# Pool_Controller-v3.net
KiCad netlist of a schematic drawn in EAGLE
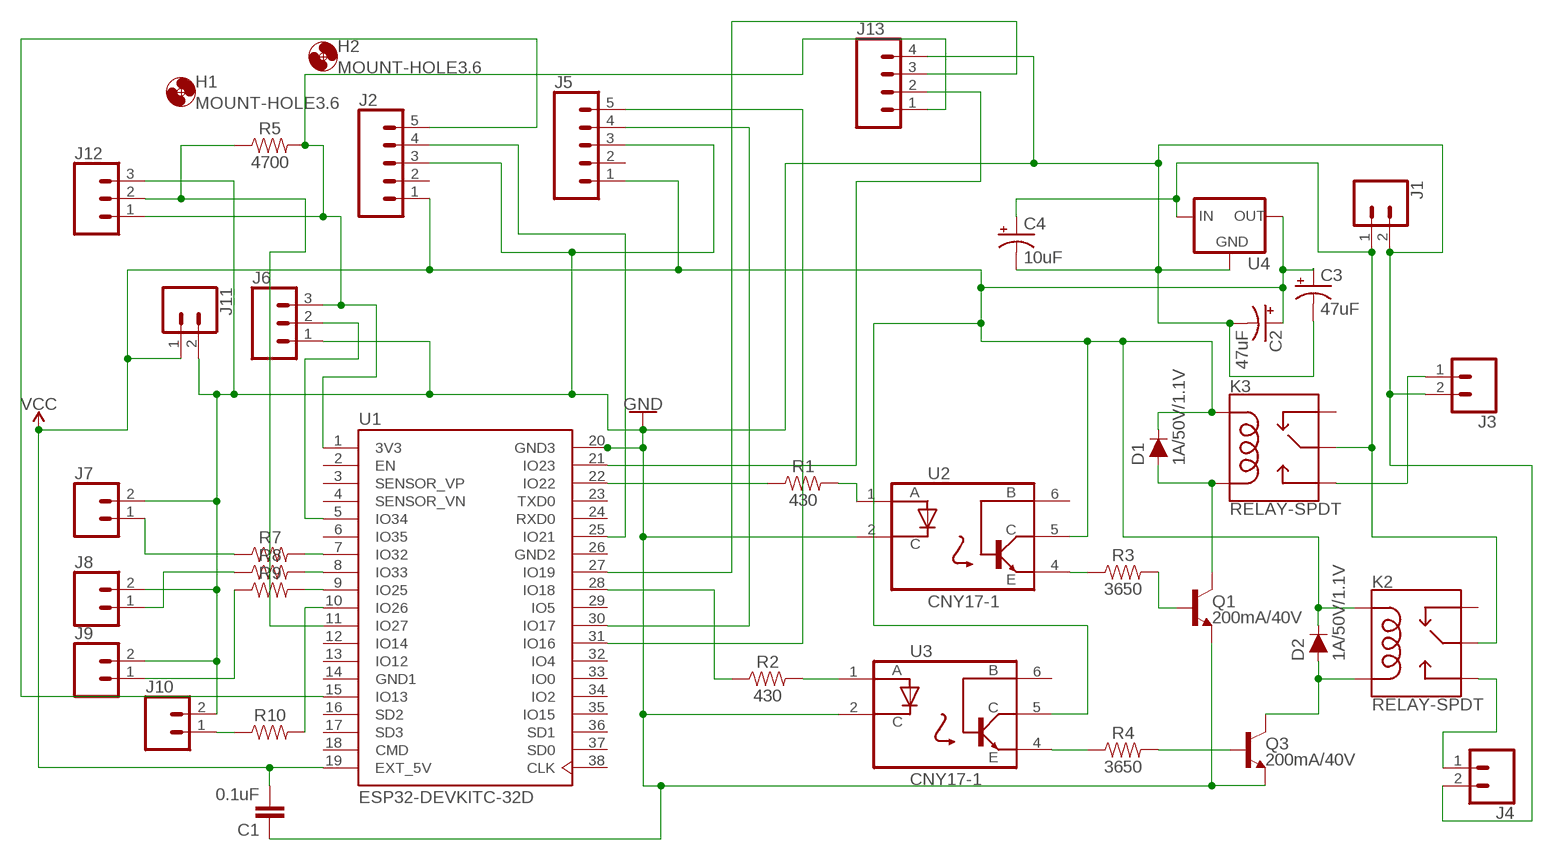
[diagram p0: schematic, sheet 1]

(export (version "E")
  (design (tool "Eeschema 10.0.6"))
  (components
    (comp (ref "C1")
      (value "0.1uF")
      (footprint "eagle-import:CAP-PTH-SMALL-KIT")
      (libsource (lib "eagle-import") (part "0.1UF-KIT-EZ-50V-20%"))
    )
    (comp (ref "C2")
      (value "47uF")
      (footprint "eagle-import:CPOL-RADIAL-2.5MM-5MM-KIT")
      (libsource (lib "eagle-import") (part "SparkFun-Capacitors_510_10UF-POLAR-RADIAL-2.5MM-KIT-25V-20%"))
    )
    (comp (ref "C3")
      (value "47uF")
      (footprint "eagle-import:CPOL-RADIAL-2.5MM-5MM")
      (libsource (lib "eagle-import") (part "10UF-POLAR-RADIAL-2.5MM-25V-20%"))
    )
    (comp (ref "C4")
      (value "10uF")
      (footprint "eagle-import:CPOL-RADIAL-2.5MM-5MM")
      (libsource (lib "eagle-import") (part "10UF-POLAR-RADIAL-2.5MM-25V-20%"))
    )
    (comp (ref "D1")
      (value "1A/50V/1.1V")
      (footprint "eagle-import:DIODE-1N4001")
      (libsource (lib "eagle-import") (part "DIODE-PTH"))
    )
    (comp (ref "D2")
      (value "1A/50V/1.1V")
      (footprint "eagle-import:DIODE-1N4001")
      (libsource (lib "eagle-import") (part "DIODE-PTH"))
    )
    (comp (ref "H1")
      (value "MOUNT-HOLE3.6")
      (footprint "eagle-import:3,6")
      (libsource (lib "eagle-import") (part "MOUNT-HOLE3.6"))
    )
    (comp (ref "H2")
      (value "MOUNT-HOLE3.6")
      (footprint "eagle-import:3,6")
      (libsource (lib "eagle-import") (part "MOUNT-HOLE3.6"))
    )
    (comp (ref "J1")
      (value "CONN_023.5MM")
      (footprint "eagle-import:SCREWTERMINAL-3.5MM-2")
      (libsource (lib "eagle-import") (part "CONN_023.5MM"))
    )
    (comp (ref "J2")
      (value "CONN_05")
      (footprint "eagle-import:1X05")
      (libsource (lib "eagle-import") (part "CONN_05"))
    )
    (comp (ref "J3")
      (value "CONN_023.5MM")
      (footprint "eagle-import:SCREWTERMINAL-3.5MM-2")
      (libsource (lib "eagle-import") (part "CONN_023.5MM"))
    )
    (comp (ref "J4")
      (value "CONN_023.5MM")
      (footprint "eagle-import:SCREWTERMINAL-3.5MM-2")
      (libsource (lib "eagle-import") (part "CONN_023.5MM"))
    )
    (comp (ref "J5")
      (value "CONN_05")
      (footprint "eagle-import:1X05")
      (libsource (lib "eagle-import") (part "CONN_05"))
    )
    (comp (ref "J6")
      (value "CONN_03SCREW")
      (footprint "eagle-import:SCREWTERMINAL-3.5MM-3")
      (libsource (lib "eagle-import") (part "CONN_03SCREW"))
    )
    (comp (ref "J7")
      (value "CONN_02")
      (footprint "eagle-import:1X02")
      (libsource (lib "eagle-import") (part "CONN_02"))
    )
    (comp (ref "J8")
      (value "CONN_02")
      (footprint "eagle-import:1X02")
      (libsource (lib "eagle-import") (part "CONN_02"))
    )
    (comp (ref "J9")
      (value "CONN_02")
      (footprint "eagle-import:1X02")
      (libsource (lib "eagle-import") (part "CONN_02"))
    )
    (comp (ref "J10")
      (value "CONN_02")
      (footprint "eagle-import:1X02")
      (libsource (lib "eagle-import") (part "CONN_02"))
    )
    (comp (ref "J11")
      (value "CONN_023.5MM")
      (footprint "eagle-import:SCREWTERMINAL-3.5MM-2")
      (libsource (lib "eagle-import") (part "CONN_023.5MM"))
    )
    (comp (ref "J12")
      (value "CONN_03SCREW")
      (footprint "eagle-import:SCREWTERMINAL-3.5MM-3")
      (libsource (lib "eagle-import") (part "CONN_03SCREW"))
    )
    (comp (ref "J13")
      (value "CONN_04SCREW")
      (footprint "eagle-import:SCREWTERMINAL-3.5MM-4")
      (libsource (lib "eagle-import") (part "CONN_04SCREW"))
    )
    (comp (ref "K2")
      (value "RELAY-SPDT")
      (footprint "eagle-import:RELAY_G5LE")
      (libsource (lib "eagle-import") (part "RELAY-SPDT"))
    )
    (comp (ref "K3")
      (value "RELAY-SPDT")
      (footprint "eagle-import:RELAY_G5LE")
      (libsource (lib "eagle-import") (part "RELAY-SPDT"))
    )
    (comp (ref "Q1")
      (value "200mA/40V")
      (footprint "eagle-import:TO-92")
      (libsource (lib "eagle-import") (part "TRANS_NPN-2N3904"))
    )
    (comp (ref "Q3")
      (value "200mA/40V")
      (footprint "eagle-import:TO-92")
      (libsource (lib "eagle-import") (part "TRANS_NPN-2N3904"))
    )
    (comp (ref "R1")
      (value "430")
      (footprint "eagle-import:AXIAL-0.3")
      (libsource (lib "eagle-import") (part "RESISTORAXIAL-0.3"))
    )
    (comp (ref "R2")
      (value "430")
      (footprint "eagle-import:AXIAL-0.3")
      (libsource (lib "eagle-import") (part "RESISTORAXIAL-0.3"))
    )
    (comp (ref "R3")
      (value "3650")
      (footprint "eagle-import:AXIAL-0.3")
      (libsource (lib "eagle-import") (part "RESISTORAXIAL-0.3"))
    )
    (comp (ref "R4")
      (value "3650")
      (footprint "eagle-import:AXIAL-0.3")
      (libsource (lib "eagle-import") (part "RESISTORAXIAL-0.3"))
    )
    (comp (ref "R5")
      (value "4700")
      (footprint "eagle-import:AXIAL-0.3")
      (libsource (lib "eagle-import") (part "SparkFun-Resistors_532_RESISTORAXIAL-0.3"))
    )
    (comp (ref "R7")
      (value "RESISTORAXIAL-0.3")
      (footprint "eagle-import:AXIAL-0.3")
      (libsource (lib "eagle-import") (part "RESISTORAXIAL-0.3"))
    )
    (comp (ref "R8")
      (value "RESISTORAXIAL-0.3")
      (footprint "eagle-import:AXIAL-0.3")
      (libsource (lib "eagle-import") (part "RESISTORAXIAL-0.3"))
    )
    (comp (ref "R9")
      (value "RESISTORAXIAL-0.3")
      (footprint "eagle-import:AXIAL-0.3")
      (libsource (lib "eagle-import") (part "RESISTORAXIAL-0.3"))
    )
    (comp (ref "R10")
      (value "RESISTORAXIAL-0.3")
      (footprint "eagle-import:AXIAL-0.3")
      (libsource (lib "eagle-import") (part "RESISTORAXIAL-0.3"))
    )
    (comp (ref "U1")
      (value "ESP32-DEVKITC-32D")
      (footprint "eagle-import:MODULE_ESP32-DEVKITC-32D")
      (fields (field (name "MF") "Espressif Systems"))
      (libsource (lib "eagle-import") (part "ESP32-DEVKITC-32D"))
    )
    (comp (ref "U2")
      (value "CNY17-1")
      (footprint "eagle-import:DIP762W50P254L730H410Q6")
      (fields (field (name "MF") "Vishay"))
      (libsource (lib "eagle-import") (part "CNY17-1"))
    )
    (comp (ref "U3")
      (value "CNY17-1")
      (footprint "eagle-import:DIP762W50P254L730H410Q6")
      (fields (field (name "MF") "Vishay"))
      (libsource (lib "eagle-import") (part "CNY17-1"))
    )
    (comp (ref "U4")
      (value "V_REG_78XXSIDE")
      (footprint "eagle-import:78XXL")
      (libsource (lib "eagle-import") (part "V_REG_78XXSIDE"))
    )
  )
  (nets
    (net (code "1") (name "/GND1") (class "Default")
      (node (ref "U1") (pin "14") (pinfunction "GND1_14") (pintype "power_in"))
    )
    (net (code "2") (name "/GND2") (class "Default")
      (node (ref "U1") (pin "26") (pinfunction "GND2_26") (pintype "power_in"))
    )
    (net (code "3") (name "GND") (class "Default")
      (node (ref "C1") (pin "1") (pinfunction "1_1") (pintype "passive"))
      (node (ref "C2") (pin "2") (pinfunction "-_2") (pintype "passive"))
      (node (ref "C3") (pin "2") (pinfunction "-_2") (pintype "passive"))
      (node (ref "C4") (pin "2") (pinfunction "-_2") (pintype "passive"))
      (node (ref "J1") (pin "2") (pinfunction "2_2") (pintype "passive"))
      (node (ref "J10") (pin "2") (pinfunction "2_2") (pintype "passive"))
      (node (ref "J11") (pin "2") (pinfunction "2_2") (pintype "passive"))
      (node (ref "J12") (pin "3") (pinfunction "3_3") (pintype "passive"))
      (node (ref "J13") (pin "4") (pinfunction "4_4") (pintype "passive"))
      (node (ref "J2") (pin "3") (pinfunction "3_3") (pintype "passive"))
      (node (ref "J3") (pin "2") (pinfunction "2_2") (pintype "passive"))
      (node (ref "J4") (pin "2") (pinfunction "2_2") (pintype "passive"))
      (node (ref "J5") (pin "3") (pinfunction "3_3") (pintype "passive"))
      (node (ref "J6") (pin "1") (pinfunction "1_1") (pintype "passive"))
      (node (ref "J7") (pin "2") (pinfunction "2_2") (pintype "passive"))
      (node (ref "J8") (pin "2") (pinfunction "2_2") (pintype "passive"))
      (node (ref "J9") (pin "2") (pinfunction "2_2") (pintype "passive"))
      (node (ref "Q1") (pin "1") (pinfunction "E_1") (pintype "passive"))
      (node (ref "Q3") (pin "1") (pinfunction "E_1") (pintype "passive"))
      (node (ref "U1") (pin "20") (pinfunction "GND3_20") (pintype "power_in"))
      (node (ref "U2") (pin "2") (pinfunction "C_2") (pintype "passive"))
      (node (ref "U3") (pin "2") (pinfunction "C_2") (pintype "passive"))
      (node (ref "U4") (pin "GND") (pinfunction "GND_GND") (pintype "input"))
    )
    (net (code "4") (name "Net-(C4-+)") (class "Default")
      (node (ref "C4") (pin "1") (pinfunction "+_1") (pintype "passive"))
      (node (ref "J1") (pin "1") (pinfunction "1_1") (pintype "passive"))
      (node (ref "K2") (pin "1") (pinfunction "MAIN_1") (pintype "bidirectional"))
      (node (ref "K3") (pin "1") (pinfunction "MAIN_1") (pintype "bidirectional"))
      (node (ref "U4") (pin "IN") (pinfunction "IN_IN") (pintype "input"))
    )
    (net (code "5") (name "Net-(K2-COIL2)") (class "Default")
      (node (ref "D2") (pin "A") (pinfunction "A_A") (pintype "passive"))
      (node (ref "K2") (pin "5") (pinfunction "COIL2_5") (pintype "bidirectional"))
      (node (ref "Q3") (pin "3") (pinfunction "C_3") (pintype "passive"))
    )
    (net (code "6") (name "Net-(K2-NO)") (class "Default")
      (node (ref "J4") (pin "1") (pinfunction "1_1") (pintype "passive"))
      (node (ref "K2") (pin "3") (pinfunction "NO_3") (pintype "bidirectional"))
    )
    (net (code "7") (name "Net-(K3-COIL2)") (class "Default")
      (node (ref "D1") (pin "A") (pinfunction "A_A") (pintype "passive"))
      (node (ref "K3") (pin "5") (pinfunction "COIL2_5") (pintype "bidirectional"))
      (node (ref "Q1") (pin "3") (pinfunction "C_3") (pintype "passive"))
    )
    (net (code "8") (name "Net-(K3-NO)") (class "Default")
      (node (ref "J3") (pin "1") (pinfunction "1_1") (pintype "passive"))
      (node (ref "K3") (pin "3") (pinfunction "NO_3") (pintype "bidirectional"))
    )
    (net (code "9") (name "Net-(Q1-B)") (class "Default")
      (node (ref "Q1") (pin "2") (pinfunction "B_2") (pintype "passive"))
      (node (ref "R3") (pin "P$2") (pinfunction "2_P$2") (pintype "passive"))
    )
    (net (code "10") (name "Net-(Q3-B)") (class "Default")
      (node (ref "Q3") (pin "2") (pinfunction "B_2") (pintype "passive"))
      (node (ref "R4") (pin "P$2") (pinfunction "2_P$2") (pintype "passive"))
    )
    (net (code "11") (name "Net-(R1-1)") (class "Default")
      (node (ref "R1") (pin "P$1") (pinfunction "1_P$1") (pintype "passive"))
      (node (ref "U1") (pin "22") (pinfunction "IO22_22") (pintype "bidirectional"))
    )
    (net (code "12") (name "Net-(R1-2)") (class "Default")
      (node (ref "R1") (pin "P$2") (pinfunction "2_P$2") (pintype "passive"))
      (node (ref "U2") (pin "1") (pinfunction "A_1") (pintype "passive"))
    )
    (net (code "13") (name "Net-(R2-1)") (class "Default")
      (node (ref "R2") (pin "P$1") (pinfunction "1_P$1") (pintype "passive"))
      (node (ref "U1") (pin "28") (pinfunction "IO18_28") (pintype "bidirectional"))
    )
    (net (code "14") (name "Net-(R2-2)") (class "Default")
      (node (ref "R2") (pin "P$2") (pinfunction "2_P$2") (pintype "passive"))
      (node (ref "U3") (pin "1") (pinfunction "A_1") (pintype "passive"))
    )
    (net (code "15") (name "Net-(R3-1)") (class "Default")
      (node (ref "R3") (pin "P$1") (pinfunction "1_P$1") (pintype "passive"))
      (node (ref "U2") (pin "4") (pinfunction "E_4") (pintype "passive"))
    )
    (net (code "16") (name "Net-(R4-1)") (class "Default")
      (node (ref "R4") (pin "P$1") (pinfunction "1_P$1") (pintype "passive"))
      (node (ref "U3") (pin "4") (pinfunction "E_4") (pintype "passive"))
    )
    (net (code "17") (name "Net-(R5-1)") (class "Default")
      (node (ref "J12") (pin "2") (pinfunction "2_2") (pintype "passive"))
      (node (ref "R5") (pin "P$1") (pinfunction "1_P$1") (pintype "passive"))
      (node (ref "U1") (pin "11") (pinfunction "IO27_11") (pintype "bidirectional"))
    )
    (net (code "18") (name "Net-(R5-2)") (class "Default")
      (node (ref "J12") (pin "1") (pinfunction "1_1") (pintype "passive"))
      (node (ref "J13") (pin "1") (pinfunction "1_1") (pintype "passive"))
      (node (ref "J6") (pin "3") (pinfunction "3_3") (pintype "passive"))
      (node (ref "R5") (pin "P$2") (pinfunction "2_P$2") (pintype "passive"))
      (node (ref "U1") (pin "1") (pinfunction "3V3_1") (pintype "power_in"))
    )
    (net (code "19") (name "Net-(R7-1)") (class "Default")
      (node (ref "J7") (pin "1") (pinfunction "1_1") (pintype "passive"))
      (node (ref "R7") (pin "P$1") (pinfunction "1_P$1") (pintype "passive"))
    )
    (net (code "20") (name "Net-(R7-2)") (class "Default")
      (node (ref "R7") (pin "P$2") (pinfunction "2_P$2") (pintype "passive"))
      (node (ref "U1") (pin "7") (pinfunction "IO32_7") (pintype "bidirectional"))
    )
    (net (code "21") (name "Net-(R8-1)") (class "Default")
      (node (ref "J8") (pin "1") (pinfunction "1_1") (pintype "passive"))
      (node (ref "R8") (pin "P$1") (pinfunction "1_P$1") (pintype "passive"))
    )
    (net (code "22") (name "Net-(R8-2)") (class "Default")
      (node (ref "R8") (pin "P$2") (pinfunction "2_P$2") (pintype "passive"))
      (node (ref "U1") (pin "8") (pinfunction "IO33_8") (pintype "bidirectional"))
    )
    (net (code "23") (name "Net-(R9-1)") (class "Default")
      (node (ref "J9") (pin "1") (pinfunction "1_1") (pintype "passive"))
      (node (ref "R9") (pin "P$1") (pinfunction "1_P$1") (pintype "passive"))
    )
    (net (code "24") (name "Net-(R9-2)") (class "Default")
      (node (ref "R9") (pin "P$2") (pinfunction "2_P$2") (pintype "passive"))
      (node (ref "U1") (pin "9") (pinfunction "IO25_9") (pintype "bidirectional"))
    )
    (net (code "25") (name "Net-(R10-1)") (class "Default")
      (node (ref "J10") (pin "1") (pinfunction "1_1") (pintype "passive"))
      (node (ref "R10") (pin "P$1") (pinfunction "1_P$1") (pintype "passive"))
    )
    (net (code "26") (name "Net-(R10-2)") (class "Default")
      (node (ref "R10") (pin "P$2") (pinfunction "2_P$2") (pintype "passive"))
      (node (ref "U1") (pin "10") (pinfunction "IO26_10") (pintype "bidirectional"))
    )
    (net (code "27") (name "Net-(U1-IO13)") (class "Default")
      (node (ref "J2") (pin "5") (pinfunction "5_5") (pintype "passive"))
      (node (ref "U1") (pin "15") (pinfunction "IO13_15") (pintype "bidirectional"))
    )
    (net (code "28") (name "Net-(U1-IO16)") (class "Default")
      (node (ref "J5") (pin "5") (pinfunction "5_5") (pintype "passive"))
      (node (ref "U1") (pin "31") (pinfunction "IO16_31") (pintype "bidirectional"))
    )
    (net (code "29") (name "Net-(U1-IO17)") (class "Default")
      (node (ref "J5") (pin "4") (pinfunction "4_4") (pintype "passive"))
      (node (ref "U1") (pin "30") (pinfunction "IO17_30") (pintype "bidirectional"))
    )
    (net (code "30") (name "Net-(U1-IO19)") (class "Default")
      (node (ref "J13") (pin "3") (pinfunction "3_3") (pintype "passive"))
      (node (ref "U1") (pin "27") (pinfunction "IO19_27") (pintype "bidirectional"))
    )
    (net (code "31") (name "Net-(U1-IO21)") (class "Default")
      (node (ref "J2") (pin "4") (pinfunction "4_4") (pintype "passive"))
      (node (ref "U1") (pin "25") (pinfunction "IO21_25") (pintype "bidirectional"))
    )
    (net (code "32") (name "Net-(U1-IO23)") (class "Default")
      (node (ref "J13") (pin "2") (pinfunction "2_2") (pintype "passive"))
      (node (ref "U1") (pin "21") (pinfunction "IO23_21") (pintype "bidirectional"))
    )
    (net (code "33") (name "Net-(U1-IO34)") (class "Default")
      (node (ref "J6") (pin "2") (pinfunction "2_2") (pintype "passive"))
      (node (ref "U1") (pin "5") (pinfunction "IO34_5") (pintype "bidirectional"))
    )
    (net (code "34") (name "VCC") (class "Default")
      (node (ref "C1") (pin "2") (pinfunction "2_2") (pintype "passive"))
      (node (ref "C2") (pin "1") (pinfunction "+_1") (pintype "passive"))
      (node (ref "C3") (pin "1") (pinfunction "+_1") (pintype "passive"))
      (node (ref "D1") (pin "C") (pinfunction "C_C") (pintype "passive"))
      (node (ref "D2") (pin "C") (pinfunction "C_C") (pintype "passive"))
      (node (ref "J11") (pin "1") (pinfunction "1_1") (pintype "passive"))
      (node (ref "J2") (pin "1") (pinfunction "1_1") (pintype "passive"))
      (node (ref "J5") (pin "1") (pinfunction "1_1") (pintype "passive"))
      (node (ref "K2") (pin "2") (pinfunction "COIL1_2") (pintype "bidirectional"))
      (node (ref "K3") (pin "2") (pinfunction "COIL1_2") (pintype "bidirectional"))
      (node (ref "U1") (pin "19") (pinfunction "EXT_5V_19") (pintype "power_in"))
      (node (ref "U2") (pin "5") (pinfunction "C`_5") (pintype "passive"))
      (node (ref "U3") (pin "5") (pinfunction "C`_5") (pintype "passive"))
      (node (ref "U4") (pin "OUT") (pinfunction "OUT_OUT") (pintype "passive"))
    )
    (net (code "35") (name "unconnected-(J2-Pad2)") (class "Default")
      (node (ref "J2") (pin "2") (pinfunction "2_2") (pintype "passive"))
    )
    (net (code "36") (name "unconnected-(J5-Pad2)") (class "Default")
      (node (ref "J5") (pin "2") (pinfunction "2_2") (pintype "passive"))
    )
    (net (code "37") (name "unconnected-(K2-NC-Pad4)") (class "Default")
      (node (ref "K2") (pin "4") (pinfunction "NC_4") (pintype "bidirectional"))
    )
    (net (code "38") (name "unconnected-(K3-NC-Pad4)") (class "Default")
      (node (ref "K3") (pin "4") (pinfunction "NC_4") (pintype "bidirectional"))
    )
    (net (code "39") (name "unconnected-(U1-CLK-Pad38)") (class "Default")
      (node (ref "U1") (pin "38") (pinfunction "CLK_38") (pintype "input"))
    )
    (net (code "40") (name "unconnected-(U1-CMD-Pad18)") (class "Default")
      (node (ref "U1") (pin "18") (pinfunction "CMD_18") (pintype "bidirectional"))
    )
    (net (code "41") (name "unconnected-(U1-EN-Pad2)") (class "Default")
      (node (ref "U1") (pin "2") (pinfunction "EN_2") (pintype "input"))
    )
    (net (code "42") (name "unconnected-(U1-IO0-Pad33)") (class "Default")
      (node (ref "U1") (pin "33") (pinfunction "IO0_33") (pintype "bidirectional"))
    )
    (net (code "43") (name "unconnected-(U1-IO2-Pad34)") (class "Default")
      (node (ref "U1") (pin "34") (pinfunction "IO2_34") (pintype "bidirectional"))
    )
    (net (code "44") (name "unconnected-(U1-IO4-Pad32)") (class "Default")
      (node (ref "U1") (pin "32") (pinfunction "IO4_32") (pintype "bidirectional"))
    )
    (net (code "45") (name "unconnected-(U1-IO5-Pad29)") (class "Default")
      (node (ref "U1") (pin "29") (pinfunction "IO5_29") (pintype "bidirectional"))
    )
    (net (code "46") (name "unconnected-(U1-IO12-Pad13)") (class "Default")
      (node (ref "U1") (pin "13") (pinfunction "IO12_13") (pintype "bidirectional"))
    )
    (net (code "47") (name "unconnected-(U1-IO14-Pad12)") (class "Default")
      (node (ref "U1") (pin "12") (pinfunction "IO14_12") (pintype "bidirectional"))
    )
    (net (code "48") (name "unconnected-(U1-IO15-Pad35)") (class "Default")
      (node (ref "U1") (pin "35") (pinfunction "IO15_35") (pintype "bidirectional"))
    )
    (net (code "49") (name "unconnected-(U1-IO35-Pad6)") (class "Default")
      (node (ref "U1") (pin "6") (pinfunction "IO35_6") (pintype "bidirectional"))
    )
    (net (code "50") (name "unconnected-(U1-RXD0-Pad24)") (class "Default")
      (node (ref "U1") (pin "24") (pinfunction "RXD0_24") (pintype "input"))
    )
    (net (code "51") (name "unconnected-(U1-SD0-Pad37)") (class "Default")
      (node (ref "U1") (pin "37") (pinfunction "SD0_37") (pintype "bidirectional"))
    )
    (net (code "52") (name "unconnected-(U1-SD1-Pad36)") (class "Default")
      (node (ref "U1") (pin "36") (pinfunction "SD1_36") (pintype "bidirectional"))
    )
    (net (code "53") (name "unconnected-(U1-SD2-Pad16)") (class "Default")
      (node (ref "U1") (pin "16") (pinfunction "SD2_16") (pintype "bidirectional"))
    )
    (net (code "54") (name "unconnected-(U1-SD3-Pad17)") (class "Default")
      (node (ref "U1") (pin "17") (pinfunction "SD3_17") (pintype "bidirectional"))
    )
    (net (code "55") (name "unconnected-(U1-SENSOR_VN-Pad4)") (class "Default")
      (node (ref "U1") (pin "4") (pinfunction "SENSOR_VN_4") (pintype "input"))
    )
    (net (code "56") (name "unconnected-(U1-SENSOR_VP-Pad3)") (class "Default")
      (node (ref "U1") (pin "3") (pinfunction "SENSOR_VP_3") (pintype "input"))
    )
    (net (code "57") (name "unconnected-(U1-TXD0-Pad23)") (class "Default")
      (node (ref "U1") (pin "23") (pinfunction "TXD0_23") (pintype "output"))
    )
    (net (code "58") (name "unconnected-(U2-B-Pad6)") (class "Default")
      (node (ref "U2") (pin "6") (pinfunction "B_6") (pintype "passive"))
    )
    (net (code "59") (name "unconnected-(U3-B-Pad6)") (class "Default")
      (node (ref "U3") (pin "6") (pinfunction "B_6") (pintype "passive"))
    )
  )
)
